# DE-250624.net
KiCad netlist of a schematic drawn in Altium Designer
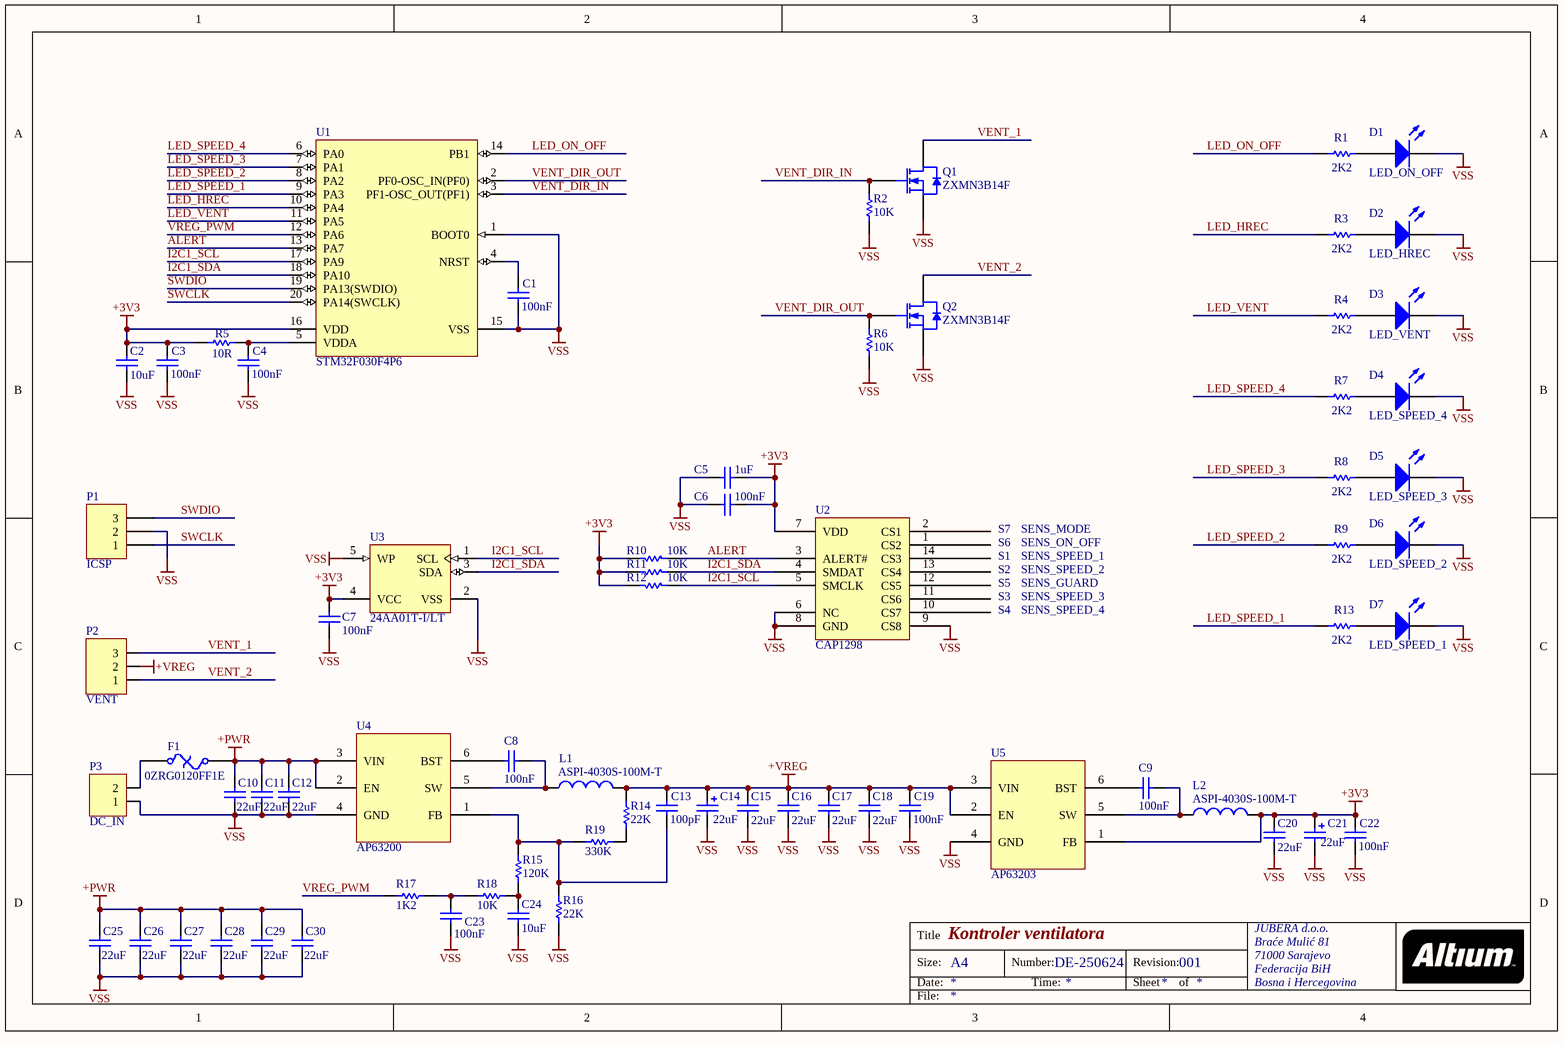
[diagram p0: DE-250624.SchDoc]

(export (version "E")
  (design (tool "Eeschema 10.0.6"))
  (components
    (comp (ref "C1")
      (value "100nF")
      (footprint "0603")
      (description "Ceramic Chip Capacitor - 25V")
      (fields (field (name "Comment") "C0603") (field (name "PUBLISHER") "Altium Limited"))
      (libsource (lib "DE-250624") (part "C0603"))
    )
    (comp (ref "C2")
      (value "10uF")
      (footprint "0805")
      (description "Ceramic Chip Capacitor - 25V")
      (fields (field (name "Comment") "C0805") (field (name "PUBLISHER") "Altium Limited"))
      (libsource (lib "DE-250624") (part "C0805"))
    )
    (comp (ref "C3")
      (value "100nF")
      (footprint "0603")
      (description "Ceramic Chip Capacitor - 25V")
      (fields (field (name "Comment") "C0603") (field (name "PUBLISHER") "Altium Limited"))
      (libsource (lib "DE-250624") (part "C0603"))
    )
    (comp (ref "C4")
      (value "100nF")
      (footprint "0603")
      (description "Ceramic Chip Capacitor - 25V")
      (fields (field (name "Comment") "C0603") (field (name "PUBLISHER") "Altium Limited"))
      (libsource (lib "DE-250624") (part "C0603"))
    )
    (comp (ref "C5")
      (value "1uF")
      (footprint "0603")
      (description "Ceramic Chip Capacitor - 25V")
      (fields (field (name "Comment") "C0603") (field (name "PUBLISHER") "Altium Limited"))
      (libsource (lib "DE-250624") (part "C0603"))
    )
    (comp (ref "C6")
      (value "100nF")
      (footprint "0603")
      (description "Ceramic Chip Capacitor - 25V")
      (fields (field (name "Comment") "C0603") (field (name "PUBLISHER") "Altium Limited"))
      (libsource (lib "DE-250624") (part "C0603"))
    )
    (comp (ref "C7")
      (value "100nF")
      (footprint "0603")
      (description "Ceramic Chip Capacitor - 25V")
      (fields (field (name "Comment") "C0603") (field (name "PUBLISHER") "Altium Limited"))
      (libsource (lib "DE-250624") (part "C0603"))
    )
    (comp (ref "C8")
      (value "100nF")
      (footprint "0603")
      (description "Ceramic Chip Capacitor - 25V")
      (fields (field (name "PUBLISHER") "Altium Limited"))
      (libsource (lib "DE-220817") (part "C0603"))
    )
    (comp (ref "C9")
      (value "100nF")
      (footprint "0603")
      (description "Ceramic Chip Capacitor - 25V")
      (fields (field (name "PUBLISHER") "Altium Limited"))
      (libsource (lib "DE-220817") (part "C0603"))
    )
    (comp (ref "C10")
      (value "22uF")
      (footprint "0805")
      (description "Ceramic Chip Capacitor - 35V")
      (fields (field (name "Comment") "C0805") (field (name "PUBLISHER") "Altium Limited"))
      (libsource (lib "DE-250624") (part "C0805"))
    )
    (comp (ref "C11")
      (value "22uF")
      (footprint "0805")
      (description "Ceramic Chip Capacitor -  35V")
      (fields (field (name "Comment") "C0805") (field (name "PUBLISHER") "Altium Limited"))
      (libsource (lib "DE-250624") (part "C0805"))
    )
    (comp (ref "C12")
      (value "22uF")
      (footprint "0805")
      (description "Ceramic Chip Capacitor - 35V")
      (fields (field (name "Comment") "C0805") (field (name "PUBLISHER") "Altium Limited"))
      (libsource (lib "DE-250624") (part "C0805"))
    )
    (comp (ref "C13")
      (value "100pF")
      (footprint "0603")
      (description "Ceramic Chip Capacitor - 25V")
      (fields (field (name "Comment") "C0603") (field (name "PUBLISHER") "Altium Limited"))
      (libsource (lib "DE-250624") (part "C0603"))
    )
    (comp (ref "C14")
      (value "22uF")
      (footprint "E (8.2 x 4.3 mm)")
      (description "Tantalum Chip Capacitor: 22uF  25VDC")
      (fields (field (name "PUBLISHER") "Altium Limited"))
      (libsource (lib "DE-250624") (part "TMCME1E226 TRF"))
    )
    (comp (ref "C15")
      (value "22uF")
      (footprint "0805")
      (description "Ceramic Chip Capacitor - 25V")
      (fields (field (name "Comment") "C0805") (field (name "PUBLISHER") "Altium Limited"))
      (libsource (lib "DE-250624") (part "C0805"))
    )
    (comp (ref "C16")
      (value "22uF")
      (footprint "0805")
      (description "Ceramic Chip Capacitor - 25V")
      (fields (field (name "Comment") "C0805") (field (name "PUBLISHER") "Altium Limited"))
      (libsource (lib "DE-250624") (part "C0805"))
    )
    (comp (ref "C17")
      (value "22uF")
      (footprint "0805")
      (description "Ceramic Chip Capacitor - 25V")
      (fields (field (name "Comment") "C0805") (field (name "PUBLISHER") "Altium Limited"))
      (libsource (lib "DE-250624") (part "C0805"))
    )
    (comp (ref "C18")
      (value "22uF")
      (footprint "0805")
      (description "Ceramic Chip Capacitor - 25V")
      (fields (field (name "Comment") "C0805") (field (name "PUBLISHER") "Altium Limited"))
      (libsource (lib "DE-250624") (part "C0805"))
    )
    (comp (ref "C19")
      (value "100nF")
      (footprint "0603")
      (description "Ceramic Chip Capacitor - 25V")
      (fields (field (name "Comment") "C0603") (field (name "PUBLISHER") "Altium Limited"))
      (libsource (lib "DE-250624") (part "C0603"))
    )
    (comp (ref "C20")
      (value "22uF")
      (footprint "0805")
      (description "Ceramic Chip Capacitor - 25V")
      (fields (field (name "Comment") "C0805") (field (name "PUBLISHER") "Altium Limited"))
      (libsource (lib "DE-250624") (part "C0805"))
    )
    (comp (ref "C21")
      (value "22uF")
      (footprint "E (8.2 x 4.3 mm)")
      (description "Tantalum Chip Capacitor: 22uF  25VDC")
      (fields (field (name "PUBLISHER") "Altium Limited"))
      (libsource (lib "DE-250624") (part "TMCME1E226 TRF"))
    )
    (comp (ref "C22")
      (value "100nF")
      (footprint "0603")
      (description "Ceramic Chip Capacitor - 25V")
      (fields (field (name "Comment") "C0603") (field (name "PUBLISHER") "Altium Limited"))
      (libsource (lib "DE-250624") (part "C0603"))
    )
    (comp (ref "C23")
      (value "100nF")
      (footprint "0603")
      (description "Ceramic Chip Capacitor - 25V")
      (fields (field (name "Comment") "C0603") (field (name "PUBLISHER") "Altium Limited"))
      (libsource (lib "DE-250624") (part "C0603"))
    )
    (comp (ref "C24")
      (value "10uF")
      (footprint "0805")
      (description "Ceramic Chip Capacitor - 25V")
      (fields (field (name "Comment") "C0805") (field (name "PUBLISHER") "Altium Limited"))
      (libsource (lib "DE-250624") (part "C0805"))
    )
    (comp (ref "C25")
      (value "22uF")
      (footprint "0805")
      (description "Ceramic Chip Capacitor - 35V")
      (fields (field (name "Comment") "C0805") (field (name "PUBLISHER") "Altium Limited"))
      (libsource (lib "DE-250624") (part "C0805"))
    )
    (comp (ref "C26")
      (value "22uF")
      (footprint "0805")
      (description "Ceramic Chip Capacitor - 35V")
      (fields (field (name "Comment") "C0805") (field (name "PUBLISHER") "Altium Limited"))
      (libsource (lib "DE-250624") (part "C0805"))
    )
    (comp (ref "C27")
      (value "22uF")
      (footprint "0805")
      (description "Ceramic Chip Capacitor - 35V")
      (fields (field (name "Comment") "C0805") (field (name "PUBLISHER") "Altium Limited"))
      (libsource (lib "DE-250624") (part "C0805"))
    )
    (comp (ref "C28")
      (value "22uF")
      (footprint "0805")
      (description "Ceramic Chip Capacitor - 35V")
      (fields (field (name "Comment") "C0805") (field (name "PUBLISHER") "Altium Limited"))
      (libsource (lib "DE-250624") (part "C0805"))
    )
    (comp (ref "C29")
      (value "22uF")
      (footprint "0805")
      (description "Ceramic Chip Capacitor - 35V")
      (fields (field (name "Comment") "C0805") (field (name "PUBLISHER") "Altium Limited"))
      (libsource (lib "DE-250624") (part "C0805"))
    )
    (comp (ref "C30")
      (value "22uF")
      (footprint "0805")
      (description "Ceramic Chip Capacitor - 35V")
      (fields (field (name "Comment") "C0805") (field (name "PUBLISHER") "Altium Limited"))
      (libsource (lib "DE-250624") (part "C0805"))
    )
    (comp (ref "D1")
      (value "LED_ON_OFF")
      (footprint "LED sa rupom")
      (description "Avago HSMW-C265")
      (fields (field (name "PUBLISHER") "Altium Limited"))
      (libsource (lib "DE-250624") (part "HSMC-C540-F0001"))
    )
    (comp (ref "D2")
      (value "LED_HREC")
      (footprint "LED sa rupom")
      (description "Avago HSML-C265")
      (fields (field (name "PUBLISHER") "Altium Limited"))
      (libsource (lib "DE-250624") (part "HSMC-C540-F0001"))
    )
    (comp (ref "D3")
      (value "LED_VENT")
      (footprint "LED sa rupom")
      (description "Avago HSMR-C265")
      (fields (field (name "PUBLISHER") "Altium Limited"))
      (libsource (lib "DE-250624") (part "HSMC-C540-F0001"))
    )
    (comp (ref "D4")
      (value "LED_SPEED_4")
      (footprint "LED sa rupom")
      (description "Avago HSMW-C265")
      (fields (field (name "PUBLISHER") "Altium Limited"))
      (libsource (lib "DE-250624") (part "HSMC-C540-F0001"))
    )
    (comp (ref "D5")
      (value "LED_SPEED_3")
      (footprint "LED sa rupom")
      (description "Avago HSMW-C265")
      (fields (field (name "PUBLISHER") "Altium Limited"))
      (libsource (lib "DE-250624") (part "HSMC-C540-F0001"))
    )
    (comp (ref "D6")
      (value "LED_SPEED_2")
      (footprint "LED sa rupom")
      (description "Avago HSMW-C265")
      (fields (field (name "PUBLISHER") "Altium Limited"))
      (libsource (lib "DE-250624") (part "HSMC-C540-F0001"))
    )
    (comp (ref "D7")
      (value "LED_SPEED_1")
      (footprint "LED sa rupom")
      (description "Avago HSMW-C265")
      (fields (field (name "PUBLISHER") "Altium Limited"))
      (libsource (lib "DE-250624") (part "HSMC-C540-F0001"))
    )
    (comp (ref "F1")
      (value "0ZRG0120FF1E")
      (footprint "PIN-W2/E2.8")
      (description "30 VDC 2 A Resettable Fuse - PPTC")
      (fields (field (name "PUBLISHER") "Altium Limited"))
      (libsource (lib "Miscellaneous Devices") (part "Fuse Thermal"))
    )
    (comp (ref "L1")
      (value "ASPI-4030S-100M-T")
      (footprint "ASPI-4030S")
      (description "Wire Wound Magnetically Shielded SMD Power Inductor")
      (fields (field (name "PUBLISHER") "Altium Limited"))
      (libsource (lib "DE-250624") (part "ASPI-4030S"))
    )
    (comp (ref "L2")
      (value "ASPI-4030S-100M-T")
      (footprint "ASPI-4030S")
      (description "Wire Wound Magnetically Shielded SMD Power Inductor")
      (fields (field (name "PUBLISHER") "Altium Limited"))
      (libsource (lib "DE-250624") (part "ASPI-4030S"))
    )
    (comp (ref "P1")
      (value "ICSP")
      (footprint "HDR1X3")
      (description "Header, 3-Pin")
      (fields (field (name "PUBLISHER") "Altium Limited"))
      (libsource (lib "Miscellaneous Connectors") (part "Header 3"))
    )
    (comp (ref "P2")
      (value "VENT")
      (footprint "TERMINAL BLOK 3")
      (description "3 pinski terminal blok konektor")
      (libsource (lib "DE-250624") (part "TERMINAL BLOK 3"))
    )
    (comp (ref "P3")
      (value "DC_IN")
      (footprint "TERMINAL BLOK 2")
      (description "Terminal blok konektor 3,5 mm")
      (libsource (lib "DE-250624") (part "TERMINAL BLOK 2"))
    )
    (comp (ref "Q1")
      (value "ZXMN3B14F")
      (footprint "SOT23_N")
      (description "N-channel Enhancement Mode Vertical D-MOSFET")
      (fields (field (name "PUBLISHER") "Altium Limited"))
      (libsource (lib "DE-250624") (part "BSS123"))
    )
    (comp (ref "Q2")
      (value "ZXMN3B14F")
      (footprint "SOT23_N")
      (description "N-channel Enhancement Mode Vertical D-MOSFET")
      (fields (field (name "PUBLISHER") "Altium Limited"))
      (libsource (lib "DE-250624") (part "BSS123"))
    )
    (comp (ref "R1")
      (value "2K2")
      (footprint "ERA-0603")
      (fields (field (name "PUBLISHER") "Altium Limited"))
      (libsource (lib "DE-250624") (part "ERAV"))
    )
    (comp (ref "R2")
      (value "10K")
      (footprint "ERA-0603")
      (fields (field (name "PUBLISHER") "Altium Limited"))
      (libsource (lib "DE-250624") (part "ERAV"))
    )
    (comp (ref "R3")
      (value "2K2")
      (footprint "ERA-0603")
      (fields (field (name "PUBLISHER") "Altium Limited"))
      (libsource (lib "DE-250624") (part "ERAV"))
    )
    (comp (ref "R4")
      (value "2K2")
      (footprint "ERA-0603")
      (fields (field (name "PUBLISHER") "Altium Limited"))
      (libsource (lib "DE-250624") (part "ERAV"))
    )
    (comp (ref "R5")
      (value "10R")
      (footprint "ERA-0603")
      (fields (field (name "PUBLISHER") "Altium Limited"))
      (libsource (lib "DE-250624") (part "ERAV"))
    )
    (comp (ref "R6")
      (value "10K")
      (footprint "ERA-0603")
      (fields (field (name "PUBLISHER") "Altium Limited"))
      (libsource (lib "DE-250624") (part "ERAV"))
    )
    (comp (ref "R7")
      (value "2K2")
      (footprint "ERA-0603")
      (fields (field (name "PUBLISHER") "Altium Limited"))
      (libsource (lib "DE-250624") (part "ERAV"))
    )
    (comp (ref "R8")
      (value "2K2")
      (footprint "ERA-0603")
      (fields (field (name "PUBLISHER") "Altium Limited"))
      (libsource (lib "DE-250624") (part "ERAV"))
    )
    (comp (ref "R9")
      (value "2K2")
      (footprint "ERA-0603")
      (fields (field (name "PUBLISHER") "Altium Limited"))
      (libsource (lib "DE-250624") (part "ERAV"))
    )
    (comp (ref "R10")
      (value "10K")
      (footprint "ERA-0603")
      (fields (field (name "PUBLISHER") "Altium Limited"))
      (libsource (lib "DE-250624") (part "ERAV"))
    )
    (comp (ref "R11")
      (value "10K")
      (footprint "ERA-0603")
      (fields (field (name "PUBLISHER") "Altium Limited"))
      (libsource (lib "DE-250624") (part "ERAV"))
    )
    (comp (ref "R12")
      (value "10K")
      (footprint "ERA-0603")
      (fields (field (name "PUBLISHER") "Altium Limited"))
      (libsource (lib "DE-250624") (part "ERAV"))
    )
    (comp (ref "R13")
      (value "2K2")
      (footprint "ERA-0603")
      (fields (field (name "PUBLISHER") "Altium Limited"))
      (libsource (lib "DE-250624") (part "ERAV"))
    )
    (comp (ref "R14")
      (value "22K")
      (footprint "ERA-0603")
      (fields (field (name "PUBLISHER") "Altium Limited"))
      (libsource (lib "DE-250624") (part "ERAV"))
    )
    (comp (ref "R15")
      (value "120K")
      (footprint "ERA-0603")
      (fields (field (name "PUBLISHER") "Altium Limited"))
      (libsource (lib "DE-250624") (part "ERAV"))
    )
    (comp (ref "R16")
      (value "22K")
      (footprint "ERA-0603")
      (fields (field (name "PUBLISHER") "Altium Limited"))
      (libsource (lib "DE-250624") (part "ERAV"))
    )
    (comp (ref "R17")
      (value "1K2")
      (footprint "ERA-0603")
      (fields (field (name "PUBLISHER") "Altium Limited"))
      (libsource (lib "DE-250624") (part "ERAV"))
    )
    (comp (ref "R18")
      (value "10K")
      (footprint "ERA-0603")
      (fields (field (name "PUBLISHER") "Altium Limited"))
      (libsource (lib "DE-250624") (part "ERAV"))
    )
    (comp (ref "R19")
      (value "330K")
      (footprint "ERA-0603")
      (fields (field (name "PUBLISHER") "Altium Limited"))
      (libsource (lib "DE-250624") (part "ERAV"))
    )
    (comp (ref "S1")
      (value "SENS_SPEED_1")
      (footprint "SENSOR_PAD")
      (libsource (lib "DE-250624") (part "Touch sensor"))
    )
    (comp (ref "S2")
      (value "SENS_SPEED_2")
      (footprint "SENSOR_PAD")
      (libsource (lib "DE-250624") (part "Touch sensor"))
    )
    (comp (ref "S3")
      (value "SENS_SPEED_3")
      (footprint "SENSOR_PAD")
      (libsource (lib "DE-250624") (part "Touch sensor"))
    )
    (comp (ref "S4")
      (value "SENS_SPEED_4")
      (footprint "SENSOR_PAD")
      (libsource (lib "DE-250624") (part "Touch sensor"))
    )
    (comp (ref "S5")
      (value "SENS_GUARD")
      (footprint "SENSOR_PAD")
      (libsource (lib "DE-250624") (part "Touch sensor"))
    )
    (comp (ref "S6")
      (value "SENS_ON_OFF")
      (footprint "SENSOR_PAD")
      (libsource (lib "DE-250624") (part "Touch sensor"))
    )
    (comp (ref "S7")
      (value "SENS_MODE")
      (footprint "SENSOR_PAD")
      (libsource (lib "DE-250624") (part "Touch sensor"))
    )
    (comp (ref "U1")
      (value "STM32F030F4P6")
      (footprint "STM-TSSOP20_N")
      (libsource (lib "STMicroelectronics STM32 F0") (part "STM32F030F4P6"))
    )
    (comp (ref "U2")
      (value "CAP1298")
      (footprint "SOIC14")
      (description "8 chanel capacitive sensor ic")
      (fields (field (name "PUBLISHER") "Altium Limited"))
      (libsource (lib "DE-250624") (part "CAP1298"))
    )
    (comp (ref "U3")
      (value "24AA01T-I/LT")
      (footprint "SC70-LT5_N")
      (description "1Kbit, 400kHz, 2.5V, I2C Serial EEPROM, 5-Pin SC70, Industrial Temperature, Tape and Reel")
      (fields (field (name "PUBLISHER") "Altium Limited"))
      (libsource (lib "Microchip Memory I2C Serial EEPROM") (part "24LC01BHT-I/LT"))
    )
    (comp (ref "U4")
      (value "AP63200")
      (footprint "TSOT-26")
      (description "2A synchronous  buck converter")
      (libsource (lib "DE-250624") (part "AP63200"))
    )
    (comp (ref "U5")
      (value "AP63203")
      (footprint "TSOT-26")
      (description "2A synchronous  buck converter")
      (libsource (lib "DE-250624") (part "AP63200"))
    )
  )
  (nets
    (net (code "1") (name "+3V3") (class "Default")
      (node (ref "C2") (pin "2") (pinfunction "2_2") (pintype "passive"))
      (node (ref "C20") (pin "2") (pinfunction "2_2") (pintype "passive"))
      (node (ref "C21") (pin "1") (pinfunction "1_1") (pintype "passive"))
      (node (ref "C22") (pin "2") (pinfunction "2_2") (pintype "passive"))
      (node (ref "C3") (pin "2") (pinfunction "2_2") (pintype "passive"))
      (node (ref "C5") (pin "1") (pinfunction "1_1") (pintype "passive"))
      (node (ref "C6") (pin "1") (pinfunction "1_1") (pintype "passive"))
      (node (ref "C7") (pin "1") (pinfunction "1_1") (pintype "passive"))
      (node (ref "L2") (pin "2") (pinfunction "2_2") (pintype "passive"))
      (node (ref "R10") (pin "2") (pinfunction "2_2") (pintype "passive"))
      (node (ref "R11") (pin "2") (pinfunction "2_2") (pintype "passive"))
      (node (ref "R12") (pin "2") (pinfunction "2_2") (pintype "passive"))
      (node (ref "R5") (pin "1") (pinfunction "1_1") (pintype "passive"))
      (node (ref "U1") (pin "16") (pinfunction "VDD_16") (pintype "power_in"))
      (node (ref "U2") (pin "7") (pinfunction "VDD_7") (pintype "power_in"))
      (node (ref "U3") (pin "4") (pinfunction "VCC_4") (pintype "power_in"))
      (node (ref "U5") (pin "1") (pinfunction "FB_1") (pintype "passive"))
    )
    (net (code "2") (name "+PWR") (class "Default")
      (node (ref "C10") (pin "2") (pinfunction "2_2") (pintype "passive"))
      (node (ref "C11") (pin "2") (pinfunction "2_2") (pintype "passive"))
      (node (ref "C12") (pin "2") (pinfunction "2_2") (pintype "passive"))
      (node (ref "C25") (pin "2") (pinfunction "2_2") (pintype "passive"))
      (node (ref "C26") (pin "2") (pinfunction "2_2") (pintype "passive"))
      (node (ref "C27") (pin "2") (pinfunction "2_2") (pintype "passive"))
      (node (ref "C28") (pin "2") (pinfunction "2_2") (pintype "passive"))
      (node (ref "C29") (pin "2") (pinfunction "2_2") (pintype "passive"))
      (node (ref "C30") (pin "2") (pinfunction "2_2") (pintype "passive"))
      (node (ref "F1") (pin "2") (pinfunction "2_2") (pintype "passive"))
      (node (ref "U4") (pin "2") (pinfunction "EN_2") (pintype "passive"))
      (node (ref "U4") (pin "3") (pinfunction "VIN_3") (pintype "power_in"))
    )
    (net (code "3") (name "+VREG") (class "Default")
      (node (ref "C13") (pin "2") (pinfunction "2_2") (pintype "passive"))
      (node (ref "C14") (pin "1") (pinfunction "1_1") (pintype "passive"))
      (node (ref "C15") (pin "2") (pinfunction "2_2") (pintype "passive"))
      (node (ref "C16") (pin "2") (pinfunction "2_2") (pintype "passive"))
      (node (ref "C17") (pin "2") (pinfunction "2_2") (pintype "passive"))
      (node (ref "C18") (pin "2") (pinfunction "2_2") (pintype "passive"))
      (node (ref "C19") (pin "2") (pinfunction "2_2") (pintype "passive"))
      (node (ref "L1") (pin "2") (pinfunction "2_2") (pintype "passive"))
      (node (ref "P2") (pin "2") (pinfunction "2_2") (pintype "passive"))
      (node (ref "R14") (pin "1") (pinfunction "1_1") (pintype "passive"))
      (node (ref "U5") (pin "2") (pinfunction "EN_2") (pintype "passive"))
      (node (ref "U5") (pin "3") (pinfunction "VIN_3") (pintype "power_in"))
    )
    (net (code "4") (name "/ALERT") (class "Default")
      (node (ref "R10") (pin "1") (pinfunction "1_1") (pintype "passive"))
      (node (ref "U1") (pin "13") (pinfunction "PA7_13") (pintype "bidirectional"))
      (node (ref "U2") (pin "3") (pinfunction "ALERT#_3") (pintype "open_collector"))
    )
    (net (code "5") (name "/I2C1_SCL") (class "Default")
      (node (ref "R12") (pin "1") (pinfunction "1_1") (pintype "passive"))
      (node (ref "U1") (pin "17") (pinfunction "PA9_17") (pintype "bidirectional"))
      (node (ref "U2") (pin "5") (pinfunction "SMCLK_5") (pintype "open_collector"))
      (node (ref "U3") (pin "1") (pinfunction "SCL_1") (pintype "input"))
    )
    (net (code "6") (name "/I2C1_SDA") (class "Default")
      (node (ref "R11") (pin "1") (pinfunction "1_1") (pintype "passive"))
      (node (ref "U1") (pin "18") (pinfunction "PA10_18") (pintype "bidirectional"))
      (node (ref "U2") (pin "4") (pinfunction "SMDAT_4") (pintype "open_collector"))
      (node (ref "U3") (pin "3") (pinfunction "SDA_3") (pintype "bidirectional"))
    )
    (net (code "7") (name "/LED_HREC") (class "Default")
      (node (ref "R3") (pin "1") (pinfunction "1_1") (pintype "passive"))
      (node (ref "U1") (pin "10") (pinfunction "PA4_10") (pintype "bidirectional"))
    )
    (net (code "8") (name "/LED_ON_OFF") (class "Default")
      (node (ref "R1") (pin "1") (pinfunction "1_1") (pintype "passive"))
      (node (ref "U1") (pin "14") (pinfunction "PB1_14") (pintype "bidirectional"))
    )
    (net (code "9") (name "/LED_SPEED_1") (class "Default")
      (node (ref "R13") (pin "1") (pinfunction "1_1") (pintype "passive"))
      (node (ref "U1") (pin "9") (pinfunction "PA3_9") (pintype "bidirectional"))
    )
    (net (code "10") (name "/LED_SPEED_2") (class "Default")
      (node (ref "R9") (pin "1") (pinfunction "1_1") (pintype "passive"))
      (node (ref "U1") (pin "8") (pinfunction "PA2_8") (pintype "bidirectional"))
    )
    (net (code "11") (name "/LED_SPEED_3") (class "Default")
      (node (ref "R8") (pin "1") (pinfunction "1_1") (pintype "passive"))
      (node (ref "U1") (pin "7") (pinfunction "PA1_7") (pintype "bidirectional"))
    )
    (net (code "12") (name "/LED_SPEED_4") (class "Default")
      (node (ref "R7") (pin "1") (pinfunction "1_1") (pintype "passive"))
      (node (ref "U1") (pin "6") (pinfunction "PA0_6") (pintype "bidirectional"))
    )
    (net (code "13") (name "/LED_VENT") (class "Default")
      (node (ref "R4") (pin "1") (pinfunction "1_1") (pintype "passive"))
      (node (ref "U1") (pin "11") (pinfunction "PA5_11") (pintype "bidirectional"))
    )
    (net (code "14") (name "/SWCLK") (class "Default")
      (node (ref "P1") (pin "1") (pinfunction "1_1") (pintype "passive"))
      (node (ref "U1") (pin "20") (pinfunction "PA14(SWCLK)_20") (pintype "bidirectional"))
    )
    (net (code "15") (name "/SWDIO") (class "Default")
      (node (ref "P1") (pin "3") (pinfunction "3_3") (pintype "passive"))
      (node (ref "U1") (pin "19") (pinfunction "PA13(SWDIO)_19") (pintype "bidirectional"))
    )
    (net (code "16") (name "/VENT_1") (class "Default")
      (node (ref "P2") (pin "3") (pinfunction "3_3") (pintype "passive"))
      (node (ref "Q1") (pin "3") (pinfunction "D_3") (pintype "passive"))
    )
    (net (code "17") (name "/VENT_2") (class "Default")
      (node (ref "P2") (pin "1") (pinfunction "1_1") (pintype "passive"))
      (node (ref "Q2") (pin "3") (pinfunction "D_3") (pintype "passive"))
    )
    (net (code "18") (name "/VENT_DIR_IN") (class "Default")
      (node (ref "Q1") (pin "1") (pinfunction "G_1") (pintype "passive"))
      (node (ref "R2") (pin "2") (pinfunction "2_2") (pintype "passive"))
      (node (ref "U1") (pin "3") (pinfunction "PF1-OSC_OUT(PF1)_3") (pintype "bidirectional"))
    )
    (net (code "19") (name "/VENT_DIR_OUT") (class "Default")
      (node (ref "Q2") (pin "1") (pinfunction "G_1") (pintype "passive"))
      (node (ref "R6") (pin "2") (pinfunction "2_2") (pintype "passive"))
      (node (ref "U1") (pin "2") (pinfunction "PF0-OSC_IN(PF0)_2") (pintype "bidirectional"))
    )
    (net (code "20") (name "/VREG_PWM") (class "Default")
      (node (ref "R17") (pin "1") (pinfunction "1_1") (pintype "passive"))
      (node (ref "U1") (pin "12") (pinfunction "PA6_12") (pintype "bidirectional"))
    )
    (net (code "21") (name "Net-(C23-Pad2)") (class "Default")
      (node (ref "C23") (pin "2") (pinfunction "2_2") (pintype "passive"))
      (node (ref "R17") (pin "2") (pinfunction "2_2") (pintype "passive"))
      (node (ref "R18") (pin "1") (pinfunction "1_1") (pintype "passive"))
    )
    (net (code "22") (name "Net-(C24-Pad2)") (class "Default")
      (node (ref "C24") (pin "2") (pinfunction "2_2") (pintype "passive"))
      (node (ref "R15") (pin "2") (pinfunction "2_2") (pintype "passive"))
      (node (ref "R18") (pin "2") (pinfunction "2_2") (pintype "passive"))
    )
    (net (code "23") (name "Net-(D1-A)") (class "Default")
      (node (ref "D1") (pin "1") (pinfunction "A_1") (pintype "passive"))
      (node (ref "R1") (pin "2") (pinfunction "2_2") (pintype "passive"))
    )
    (net (code "24") (name "Net-(D2-A)") (class "Default")
      (node (ref "D2") (pin "1") (pinfunction "A_1") (pintype "passive"))
      (node (ref "R3") (pin "2") (pinfunction "2_2") (pintype "passive"))
    )
    (net (code "25") (name "Net-(D3-A)") (class "Default")
      (node (ref "D3") (pin "1") (pinfunction "A_1") (pintype "passive"))
      (node (ref "R4") (pin "2") (pinfunction "2_2") (pintype "passive"))
    )
    (net (code "26") (name "Net-(D4-A)") (class "Default")
      (node (ref "D4") (pin "1") (pinfunction "A_1") (pintype "passive"))
      (node (ref "R7") (pin "2") (pinfunction "2_2") (pintype "passive"))
    )
    (net (code "27") (name "Net-(D5-A)") (class "Default")
      (node (ref "D5") (pin "1") (pinfunction "A_1") (pintype "passive"))
      (node (ref "R8") (pin "2") (pinfunction "2_2") (pintype "passive"))
    )
    (net (code "28") (name "Net-(D6-A)") (class "Default")
      (node (ref "D6") (pin "1") (pinfunction "A_1") (pintype "passive"))
      (node (ref "R9") (pin "2") (pinfunction "2_2") (pintype "passive"))
    )
    (net (code "29") (name "Net-(D7-A)") (class "Default")
      (node (ref "D7") (pin "1") (pinfunction "A_1") (pintype "passive"))
      (node (ref "R13") (pin "2") (pinfunction "2_2") (pintype "passive"))
    )
    (net (code "30") (name "Net-(F1-Pad1)") (class "Default")
      (node (ref "F1") (pin "1") (pinfunction "1_1") (pintype "passive"))
      (node (ref "P3") (pin "2") (pinfunction "2_2") (pintype "passive"))
    )
    (net (code "31") (name "Net-(R14-Pad2)") (class "Default")
      (node (ref "R14") (pin "2") (pinfunction "2_2") (pintype "passive"))
      (node (ref "R19") (pin "2") (pinfunction "2_2") (pintype "passive"))
    )
    (net (code "32") (name "Net-(U1-NRST)") (class "Default")
      (node (ref "C1") (pin "2") (pinfunction "2_2") (pintype "passive"))
      (node (ref "U1") (pin "4") (pinfunction "NRST_4") (pintype "bidirectional"))
    )
    (net (code "33") (name "Net-(U1-VDDA)") (class "Default")
      (node (ref "C4") (pin "2") (pinfunction "2_2") (pintype "passive"))
      (node (ref "R5") (pin "2") (pinfunction "2_2") (pintype "passive"))
      (node (ref "U1") (pin "5") (pinfunction "VDDA_5") (pintype "power_in"))
    )
    (net (code "34") (name "Net-(U2-CS1)") (class "Default")
      (node (ref "S7") (pin "1") (pinfunction "1_1") (pintype "passive"))
      (node (ref "U2") (pin "2") (pinfunction "CS1_2") (pintype "passive"))
    )
    (net (code "35") (name "Net-(U2-CS2)") (class "Default")
      (node (ref "S6") (pin "1") (pinfunction "1_1") (pintype "passive"))
      (node (ref "U2") (pin "1") (pinfunction "CS2_1") (pintype "passive"))
    )
    (net (code "36") (name "Net-(U2-CS3)") (class "Default")
      (node (ref "S1") (pin "1") (pinfunction "1_1") (pintype "passive"))
      (node (ref "U2") (pin "14") (pinfunction "CS3_14") (pintype "passive"))
    )
    (net (code "37") (name "Net-(U2-CS4)") (class "Default")
      (node (ref "S2") (pin "1") (pinfunction "1_1") (pintype "passive"))
      (node (ref "U2") (pin "13") (pinfunction "CS4_13") (pintype "passive"))
    )
    (net (code "38") (name "Net-(U2-CS5)") (class "Default")
      (node (ref "S5") (pin "1") (pinfunction "1_1") (pintype "passive"))
      (node (ref "U2") (pin "12") (pinfunction "CS5_12") (pintype "passive"))
    )
    (net (code "39") (name "Net-(U2-CS6)") (class "Default")
      (node (ref "S3") (pin "1") (pinfunction "1_1") (pintype "passive"))
      (node (ref "U2") (pin "11") (pinfunction "CS6_11") (pintype "passive"))
    )
    (net (code "40") (name "Net-(U2-CS7)") (class "Default")
      (node (ref "S4") (pin "1") (pinfunction "1_1") (pintype "passive"))
      (node (ref "U2") (pin "10") (pinfunction "CS7_10") (pintype "passive"))
    )
    (net (code "41") (name "Net-(U4-BST)") (class "Default")
      (node (ref "C8") (pin "2") (pinfunction "2_2") (pintype "passive"))
      (node (ref "U4") (pin "6") (pinfunction "BST_6") (pintype "passive"))
    )
    (net (code "42") (name "Net-(U4-FB)") (class "Default")
      (node (ref "C13") (pin "1") (pinfunction "1_1") (pintype "passive"))
      (node (ref "R15") (pin "1") (pinfunction "1_1") (pintype "passive"))
      (node (ref "R16") (pin "2") (pinfunction "2_2") (pintype "passive"))
      (node (ref "R19") (pin "1") (pinfunction "1_1") (pintype "passive"))
      (node (ref "U4") (pin "1") (pinfunction "FB_1") (pintype "passive"))
    )
    (net (code "43") (name "Net-(U4-SW)") (class "Default")
      (node (ref "C8") (pin "1") (pinfunction "1_1") (pintype "passive"))
      (node (ref "L1") (pin "1") (pinfunction "1_1") (pintype "passive"))
      (node (ref "U4") (pin "5") (pinfunction "SW_5") (pintype "passive"))
    )
    (net (code "44") (name "Net-(U5-BST)") (class "Default")
      (node (ref "C9") (pin "2") (pinfunction "2_2") (pintype "passive"))
      (node (ref "U5") (pin "6") (pinfunction "BST_6") (pintype "passive"))
    )
    (net (code "45") (name "Net-(U5-SW)") (class "Default")
      (node (ref "C9") (pin "1") (pinfunction "1_1") (pintype "passive"))
      (node (ref "L2") (pin "1") (pinfunction "1_1") (pintype "passive"))
      (node (ref "U5") (pin "5") (pinfunction "SW_5") (pintype "passive"))
    )
    (net (code "46") (name "VSS") (class "Default")
      (node (ref "C1") (pin "1") (pinfunction "1_1") (pintype "passive"))
      (node (ref "C10") (pin "1") (pinfunction "1_1") (pintype "passive"))
      (node (ref "C11") (pin "1") (pinfunction "1_1") (pintype "passive"))
      (node (ref "C12") (pin "1") (pinfunction "1_1") (pintype "passive"))
      (node (ref "C14") (pin "2") (pinfunction "2_2") (pintype "passive"))
      (node (ref "C15") (pin "1") (pinfunction "1_1") (pintype "passive"))
      (node (ref "C16") (pin "1") (pinfunction "1_1") (pintype "passive"))
      (node (ref "C17") (pin "1") (pinfunction "1_1") (pintype "passive"))
      (node (ref "C18") (pin "1") (pinfunction "1_1") (pintype "passive"))
      (node (ref "C19") (pin "1") (pinfunction "1_1") (pintype "passive"))
      (node (ref "C2") (pin "1") (pinfunction "1_1") (pintype "passive"))
      (node (ref "C20") (pin "1") (pinfunction "1_1") (pintype "passive"))
      (node (ref "C21") (pin "2") (pinfunction "2_2") (pintype "passive"))
      (node (ref "C22") (pin "1") (pinfunction "1_1") (pintype "passive"))
      (node (ref "C23") (pin "1") (pinfunction "1_1") (pintype "passive"))
      (node (ref "C24") (pin "1") (pinfunction "1_1") (pintype "passive"))
      (node (ref "C25") (pin "1") (pinfunction "1_1") (pintype "passive"))
      (node (ref "C26") (pin "1") (pinfunction "1_1") (pintype "passive"))
      (node (ref "C27") (pin "1") (pinfunction "1_1") (pintype "passive"))
      (node (ref "C28") (pin "1") (pinfunction "1_1") (pintype "passive"))
      (node (ref "C29") (pin "1") (pinfunction "1_1") (pintype "passive"))
      (node (ref "C3") (pin "1") (pinfunction "1_1") (pintype "passive"))
      (node (ref "C30") (pin "1") (pinfunction "1_1") (pintype "passive"))
      (node (ref "C4") (pin "1") (pinfunction "1_1") (pintype "passive"))
      (node (ref "C5") (pin "2") (pinfunction "2_2") (pintype "passive"))
      (node (ref "C6") (pin "2") (pinfunction "2_2") (pintype "passive"))
      (node (ref "C7") (pin "2") (pinfunction "2_2") (pintype "passive"))
      (node (ref "D1") (pin "2") (pinfunction "K_2") (pintype "passive"))
      (node (ref "D2") (pin "2") (pinfunction "K_2") (pintype "passive"))
      (node (ref "D3") (pin "2") (pinfunction "K_2") (pintype "passive"))
      (node (ref "D4") (pin "2") (pinfunction "K_2") (pintype "passive"))
      (node (ref "D5") (pin "2") (pinfunction "K_2") (pintype "passive"))
      (node (ref "D6") (pin "2") (pinfunction "K_2") (pintype "passive"))
      (node (ref "D7") (pin "2") (pinfunction "K_2") (pintype "passive"))
      (node (ref "P1") (pin "2") (pinfunction "2_2") (pintype "passive"))
      (node (ref "P3") (pin "1") (pinfunction "1_1") (pintype "passive"))
      (node (ref "Q1") (pin "2") (pinfunction "S_2") (pintype "passive"))
      (node (ref "Q2") (pin "2") (pinfunction "S_2") (pintype "passive"))
      (node (ref "R16") (pin "1") (pinfunction "1_1") (pintype "passive"))
      (node (ref "R2") (pin "1") (pinfunction "1_1") (pintype "passive"))
      (node (ref "R6") (pin "1") (pinfunction "1_1") (pintype "passive"))
      (node (ref "U1") (pin "1") (pinfunction "BOOT0_1") (pintype "input"))
      (node (ref "U1") (pin "15") (pinfunction "VSS_15") (pintype "power_in"))
      (node (ref "U2") (pin "6") (pinfunction "NC_6") (pintype "passive"))
      (node (ref "U2") (pin "8") (pinfunction "GND_8") (pintype "power_in"))
      (node (ref "U2") (pin "9") (pinfunction "CS8_9") (pintype "passive"))
      (node (ref "U3") (pin "2") (pinfunction "VSS_2") (pintype "power_in"))
      (node (ref "U3") (pin "5") (pinfunction "WP_5") (pintype "input"))
      (node (ref "U4") (pin "4") (pinfunction "GND_4") (pintype "power_in"))
      (node (ref "U5") (pin "4") (pinfunction "GND_4") (pintype "power_in"))
    )
  )
)
